# Tape_IF_frontend.net
KiCad netlist of a schematic drawn in EAGLE
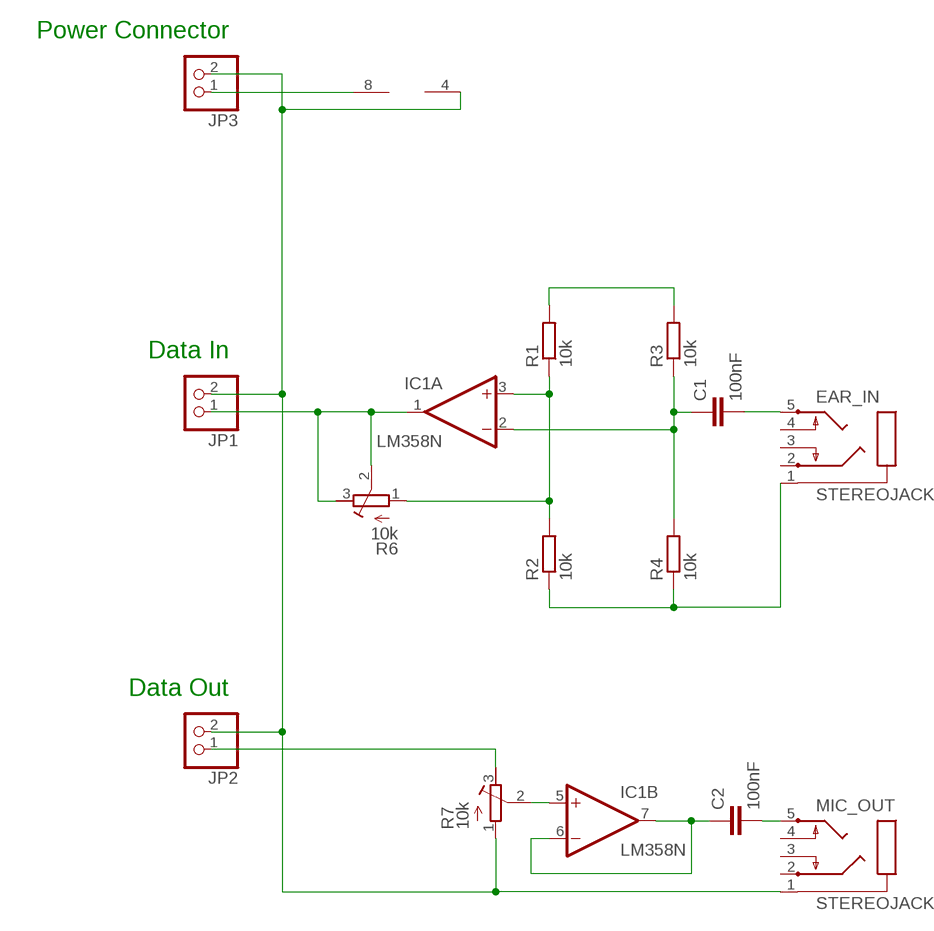
[diagram p0: schematic, sheet 1]

(export (version "E")
  (design (tool "Eeschema 10.0.6"))
  (components
    (comp (ref "C1")
      (value "100nF")
      (footprint "eagle-import:C050-025X075")
      (libsource (lib "eagle-import") (part "C-EU050-025X075"))
    )
    (comp (ref "C2")
      (value "100nF")
      (footprint "eagle-import:C050-025X075")
      (libsource (lib "eagle-import") (part "C-EU050-025X075"))
    )
    (comp (ref "EAR_IN")
      (value "STEREOJACK")
      (footprint "eagle-import:STX3100")
      (libsource (lib "eagle-import") (part "STEREOJACK"))
    )
    (comp (ref "IC1")
      (value "LM358N")
      (footprint "eagle-import:DIL08")
      (libsource (lib "eagle-import") (part "LM358N"))
    )
    (comp (ref "JP1")
      (value "PINHD-1X2")
      (footprint "eagle-import:1X02")
      (libsource (lib "eagle-import") (part "PINHD-1X2"))
    )
    (comp (ref "JP2")
      (value "PINHD-1X2")
      (footprint "eagle-import:1X02")
      (libsource (lib "eagle-import") (part "PINHD-1X2"))
    )
    (comp (ref "JP3")
      (value "PINHD-1X2")
      (footprint "eagle-import:1X02")
      (libsource (lib "eagle-import") (part "PINHD-1X2"))
    )
    (comp (ref "MIC_OUT")
      (value "STEREOJACK")
      (footprint "eagle-import:STX3100")
      (libsource (lib "eagle-import") (part "STEREOJACK"))
    )
    (comp (ref "R1")
      (value "10k")
      (footprint "eagle-import:0207_10")
      (libsource (lib "eagle-import") (part "R-EU_0207/10"))
    )
    (comp (ref "R2")
      (value "10k")
      (footprint "eagle-import:0207_10")
      (libsource (lib "eagle-import") (part "R-EU_0207/10"))
    )
    (comp (ref "R3")
      (value "10k")
      (footprint "eagle-import:0207_10")
      (libsource (lib "eagle-import") (part "R-EU_0207/10"))
    )
    (comp (ref "R4")
      (value "10k")
      (footprint "eagle-import:0207_10")
      (libsource (lib "eagle-import") (part "R-EU_0207/10"))
    )
    (comp (ref "R6")
      (value "10k")
      (footprint "eagle-import:RTRIM64W")
      (libsource (lib "eagle-import") (part "R-TRIMM64W"))
    )
    (comp (ref "R7")
      (value "10k")
      (footprint "eagle-import:RTRIM64W")
      (libsource (lib "eagle-import") (part "R-TRIMM64W"))
    )
  )
  (nets
    (net (code "1") (name "Net-(C1-Pad2)") (class "Default")
      (node (ref "C1") (pin "2") (pinfunction "2_2") (pintype "passive"))
      (node (ref "EAR_IN") (pin "5") (pinfunction "5_5") (pintype "passive"))
    )
    (net (code "2") (name "Net-(C2-Pad2)") (class "Default")
      (node (ref "C2") (pin "2") (pinfunction "2_2") (pintype "passive"))
      (node (ref "MIC_OUT") (pin "5") (pinfunction "5_5") (pintype "passive"))
    )
    (net (code "3") (name "Net-(EAR_IN-Pad1)") (class "Default")
      (node (ref "EAR_IN") (pin "1") (pinfunction "1_1") (pintype "passive"))
      (node (ref "R2") (pin "1") (pinfunction "1_1") (pintype "passive"))
      (node (ref "R4") (pin "1") (pinfunction "1_1") (pintype "passive"))
    )
    (net (code "4") (name "Net-(IC1A-+IN)") (class "Default")
      (node (ref "IC1") (pin "3") (pinfunction "+IN_3") (pintype "input"))
      (node (ref "R1") (pin "1") (pinfunction "1_1") (pintype "passive"))
      (node (ref "R2") (pin "2") (pinfunction "2_2") (pintype "passive"))
      (node (ref "R6") (pin "1") (pinfunction "A_1") (pintype "passive"))
    )
    (net (code "5") (name "Net-(IC1A--IN)") (class "Default")
      (node (ref "C1") (pin "1") (pinfunction "1_1") (pintype "passive"))
      (node (ref "IC1") (pin "2") (pinfunction "-IN_2") (pintype "input"))
      (node (ref "R3") (pin "1") (pinfunction "1_1") (pintype "passive"))
      (node (ref "R4") (pin "2") (pinfunction "2_2") (pintype "passive"))
    )
    (net (code "6") (name "Net-(IC1A-OUT)") (class "Default")
      (node (ref "IC1") (pin "1") (pinfunction "OUT_1") (pintype "output"))
      (node (ref "JP1") (pin "1") (pinfunction "1_1") (pintype "passive"))
      (node (ref "R6") (pin "2") (pinfunction "S_2") (pintype "passive"))
      (node (ref "R6") (pin "3") (pinfunction "E_3") (pintype "passive"))
    )
    (net (code "7") (name "Net-(IC1B-+IN)") (class "Default")
      (node (ref "IC1") (pin "5") (pinfunction "+IN_5") (pintype "input"))
      (node (ref "R7") (pin "2") (pinfunction "S_2") (pintype "passive"))
    )
    (net (code "8") (name "Net-(IC1B--IN)") (class "Default")
      (node (ref "C2") (pin "1") (pinfunction "1_1") (pintype "passive"))
      (node (ref "IC1") (pin "6") (pinfunction "-IN_6") (pintype "input"))
      (node (ref "IC1") (pin "7") (pinfunction "OUT_7") (pintype "output"))
    )
    (net (code "9") (name "Net-(IC1C-V+)") (class "Default")
      (node (ref "IC1") (pin "8") (pinfunction "V+_8") (pintype "power_in"))
      (node (ref "JP3") (pin "1") (pinfunction "1_1") (pintype "passive"))
    )
    (net (code "10") (name "Net-(IC1C-V-)") (class "Default")
      (node (ref "IC1") (pin "4") (pinfunction "V-_4") (pintype "power_in"))
      (node (ref "JP1") (pin "2") (pinfunction "2_2") (pintype "passive"))
      (node (ref "JP2") (pin "2") (pinfunction "2_2") (pintype "passive"))
      (node (ref "JP3") (pin "2") (pinfunction "2_2") (pintype "passive"))
      (node (ref "MIC_OUT") (pin "1") (pinfunction "1_1") (pintype "passive"))
      (node (ref "R7") (pin "1") (pinfunction "A_1") (pintype "passive"))
    )
    (net (code "11") (name "Net-(R1-Pad2)") (class "Default")
      (node (ref "R1") (pin "2") (pinfunction "2_2") (pintype "passive"))
      (node (ref "R3") (pin "2") (pinfunction "2_2") (pintype "passive"))
    )
    (net (code "12") (name "Net-(R7-E)") (class "Default")
      (node (ref "JP2") (pin "1") (pinfunction "1_1") (pintype "passive"))
      (node (ref "R7") (pin "3") (pinfunction "E_3") (pintype "passive"))
    )
    (net (code "13") (name "unconnected-(EAR_IN-Pad2)") (class "Default")
      (node (ref "EAR_IN") (pin "2") (pinfunction "2_2") (pintype "passive"))
    )
    (net (code "14") (name "unconnected-(EAR_IN-Pad3)") (class "Default")
      (node (ref "EAR_IN") (pin "3") (pinfunction "3_3") (pintype "passive"))
    )
    (net (code "15") (name "unconnected-(EAR_IN-Pad4)") (class "Default")
      (node (ref "EAR_IN") (pin "4") (pinfunction "4_4") (pintype "passive"))
    )
    (net (code "16") (name "unconnected-(MIC_OUT-Pad2)") (class "Default")
      (node (ref "MIC_OUT") (pin "2") (pinfunction "2_2") (pintype "passive"))
    )
    (net (code "17") (name "unconnected-(MIC_OUT-Pad3)") (class "Default")
      (node (ref "MIC_OUT") (pin "3") (pinfunction "3_3") (pintype "passive"))
    )
    (net (code "18") (name "unconnected-(MIC_OUT-Pad4)") (class "Default")
      (node (ref "MIC_OUT") (pin "4") (pinfunction "4_4") (pintype "passive"))
    )
  )
)
